# Adafruit_WICED_WiFi_Feather.net
KiCad netlist of a schematic drawn in EAGLE
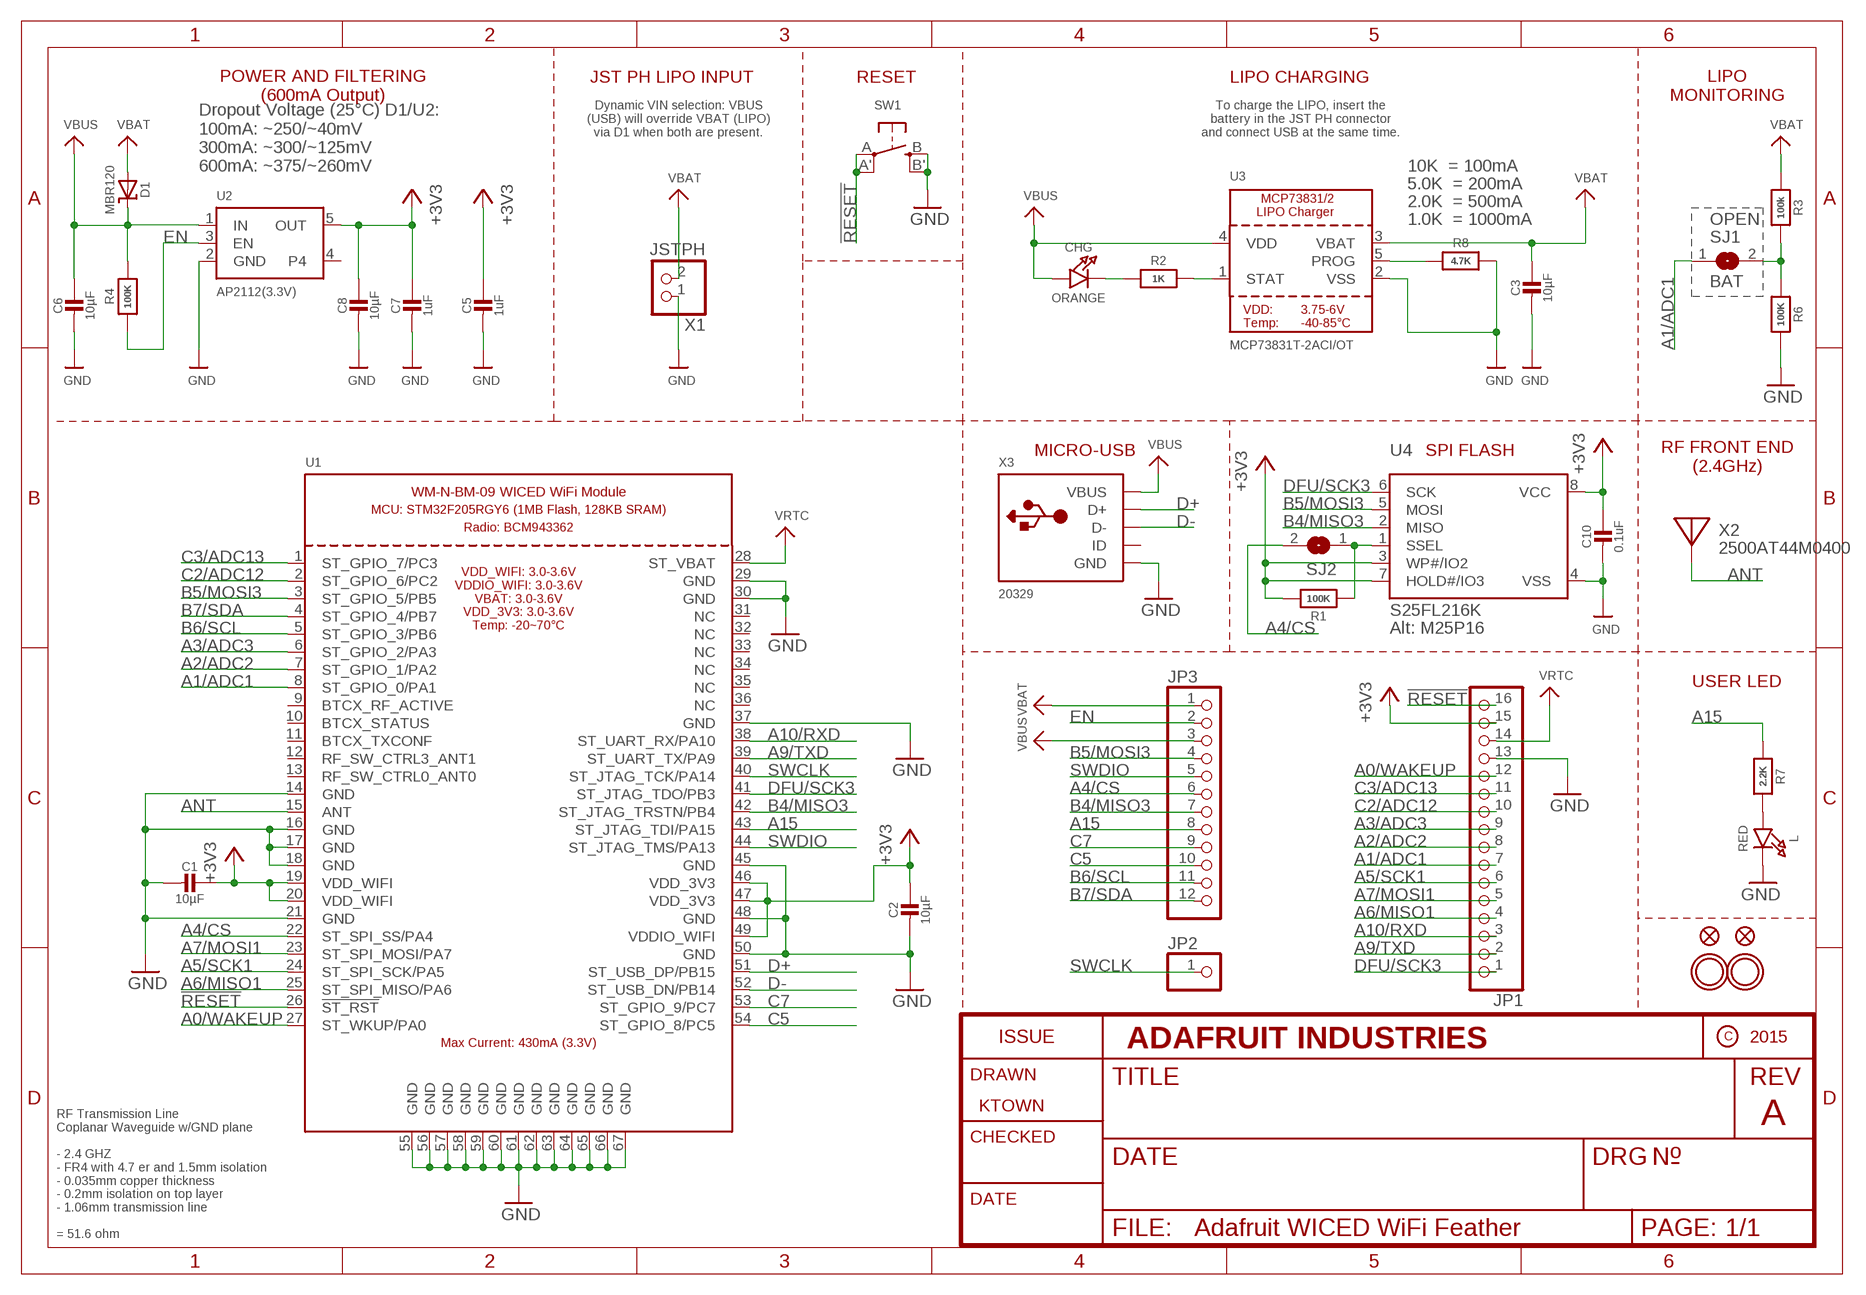
[diagram p0: schematic, sheet 1]

(export (version "E")
  (design (tool "Eeschema 10.0.6"))
  (components
    (comp (ref "C1")
      (value "10µF")
      (footprint "eagle-import:0805-NO")
      (libsource (lib "eagle-import") (part "CAP_CERAMIC0805-NOOUTLINE"))
    )
    (comp (ref "C2")
      (value "10µF")
      (footprint "eagle-import:0805-NO")
      (libsource (lib "eagle-import") (part "CAP_CERAMIC0805-NOOUTLINE"))
    )
    (comp (ref "C3")
      (value "10µF")
      (footprint "eagle-import:0805-NO")
      (libsource (lib "eagle-import") (part "CAP_CERAMIC0805-NOOUTLINE"))
    )
    (comp (ref "C5")
      (value "1uF")
      (footprint "eagle-import:0603-NO")
      (libsource (lib "eagle-import") (part "CAP_CERAMIC0603_NO"))
    )
    (comp (ref "C6")
      (value "10µF")
      (footprint "eagle-import:0805-NO")
      (libsource (lib "eagle-import") (part "CAP_CERAMIC0805-NOOUTLINE"))
    )
    (comp (ref "C7")
      (value "1uF")
      (footprint "eagle-import:0603-NO")
      (libsource (lib "eagle-import") (part "CAP_CERAMIC0603_NO"))
    )
    (comp (ref "C8")
      (value "10µF")
      (footprint "eagle-import:0805-NO")
      (libsource (lib "eagle-import") (part "CAP_CERAMIC0805-NOOUTLINE"))
    )
    (comp (ref "C10")
      (value "0.1uF")
      (footprint "eagle-import:0805_10MGAP")
      (libsource (lib "eagle-import") (part "CAP_CERAMIC0805_10MGAP"))
    )
    (comp (ref "CHG")
      (value "ORANGE")
      (footprint "eagle-import:CHIPLED_0805_NOOUTLINE")
      (libsource (lib "eagle-import") (part "LED0805_NOOUTLINE"))
    )
    (comp (ref "D1")
      (value "MBR120")
      (footprint "eagle-import:SOD-123")
      (libsource (lib "eagle-import") (part "DIODE-SCHOTTKYSOD-123"))
    )
    (comp (ref "JP1")
      (value "HEADER-1X16ROUND")
      (footprint "eagle-import:1X16_ROUND")
      (libsource (lib "eagle-import") (part "HEADER-1X16ROUND"))
    )
    (comp (ref "JP2")
      (value "HEADER-1X1ROUND")
      (footprint "eagle-import:1X01_ROUND")
      (libsource (lib "eagle-import") (part "HEADER-1X1ROUND"))
    )
    (comp (ref "JP3")
      (value "HEADER-1X12")
      (footprint "eagle-import:1X12_ROUND")
      (libsource (lib "eagle-import") (part "HEADER-1X12"))
    )
    (comp (ref "L")
      (value "RED")
      (footprint "eagle-import:CHIPLED_0805_NOOUTLINE")
      (libsource (lib "eagle-import") (part "LED0805_NOOUTLINE"))
    )
    (comp (ref "R1")
      (value "100K")
      (footprint "eagle-import:0603-NO")
      (libsource (lib "eagle-import") (part "RESISTOR_0603_NOOUT"))
    )
    (comp (ref "R2")
      (value "1K")
      (footprint "eagle-import:0603-NO")
      (libsource (lib "eagle-import") (part "RESISTOR_0603_NOOUT"))
    )
    (comp (ref "R3")
      (value "100k")
      (footprint "eagle-import:0603-NO")
      (libsource (lib "eagle-import") (part "RESISTOR_0603_NOOUT"))
    )
    (comp (ref "R4")
      (value "100K")
      (footprint "eagle-import:0603-NO")
      (libsource (lib "eagle-import") (part "RESISTOR_0603_NOOUT"))
    )
    (comp (ref "R6")
      (value "100K")
      (footprint "eagle-import:0603-NO")
      (libsource (lib "eagle-import") (part "RESISTOR_0603_NOOUT"))
    )
    (comp (ref "R7")
      (value "2.2K")
      (footprint "eagle-import:0603-NO")
      (libsource (lib "eagle-import") (part "RESISTOR_0603_NOOUT"))
    )
    (comp (ref "R8")
      (value "4.7K")
      (footprint "eagle-import:0603-NO")
      (libsource (lib "eagle-import") (part "RESISTOR_0603_NOOUT"))
    )
    (comp (ref "SJ1")
      (value "BAT")
      (footprint "eagle-import:SOLDERJUMPER_REFLOW_NOPASTE")
      (libsource (lib "eagle-import") (part "SOLDERJUMPERREFLOW_NOPASTE"))
    )
    (comp (ref "SJ2")
      (value "SOLDERJUMPER")
      (footprint "eagle-import:SOLDERJUMPER_ARROW_NOPASTE")
      (libsource (lib "eagle-import") (part "SOLDERJUMPER"))
    )
    (comp (ref "SW1")
      (value "SWITCH_TACT_SMT4.6X2.8")
      (footprint "eagle-import:BTN_KMR2_4.6X2.8")
      (libsource (lib "eagle-import") (part "SWITCH_TACT_SMT4.6X2.8"))
    )
    (comp (ref "U$31")
      (value "MOUNTINGHOLE2.5")
      (footprint "eagle-import:MOUNTINGHOLE_2.5_PLATED")
      (libsource (lib "eagle-import") (part "MOUNTINGHOLE2.5"))
    )
    (comp (ref "U$32")
      (value "MOUNTINGHOLE2.5")
      (footprint "eagle-import:MOUNTINGHOLE_2.5_PLATED")
      (libsource (lib "eagle-import") (part "MOUNTINGHOLE2.5"))
    )
    (comp (ref "U$34")
      (value "FIDUCIAL\"\"")
      (footprint "eagle-import:FIDUCIAL_1MM")
      (libsource (lib "eagle-import") (part "FIDUCIAL{dblquote}{dblquote}"))
    )
    (comp (ref "U$35")
      (value "FIDUCIAL\"\"")
      (footprint "eagle-import:FIDUCIAL_1MM")
      (libsource (lib "eagle-import") (part "FIDUCIAL{dblquote}{dblquote}"))
    )
    (comp (ref "U1")
      (value "USI_WM-N-BM-09")
      (footprint "eagle-import:USI_WM-N-BM-09")
      (libsource (lib "eagle-import") (part "USI_WM-N-BM-09"))
    )
    (comp (ref "U2")
      (value "AP2112(3.3V)")
      (footprint "eagle-import:SOT23-5")
      (libsource (lib "eagle-import") (part "VREG_SOT23-5"))
    )
    (comp (ref "U3")
      (value "MCP73831T-2ACI/OT")
      (footprint "eagle-import:SOT23-5")
      (libsource (lib "eagle-import") (part "MCP73831/2"))
    )
    (comp (ref "U4")
      (value "S25FL216K")
      (footprint "eagle-import:SOIC8_150MIL")
      (libsource (lib "eagle-import") (part "SPIFLASH_SOIC8"))
    )
    (comp (ref "X1")
      (value "JSTPH")
      (footprint "eagle-import:JSTPH2")
      (libsource (lib "eagle-import") (part "CON_JST_PH_2PIN"))
    )
    (comp (ref "X2")
      (value "2500AT44M0400")
      (footprint "eagle-import:ANT_2500AT44M0400")
      (libsource (lib "eagle-import") (part "ANTENNA_JOHANSON_2500AT44M0400"))
    )
    (comp (ref "X3")
      (value "20329")
      (footprint "eagle-import:4UCONN_20329_V2")
      (libsource (lib "eagle-import") (part "USB_MICRO_20329_V2"))
    )
  )
  (nets
    (net (code "1") (name "+3V3") (class "Default")
      (node (ref "C1") (pin "1") (pinfunction "1_1") (pintype "passive"))
      (node (ref "C10") (pin "1") (pinfunction "1_1") (pintype "passive"))
      (node (ref "C2") (pin "1") (pinfunction "1_1") (pintype "passive"))
      (node (ref "C5") (pin "1") (pinfunction "1_1") (pintype "passive"))
      (node (ref "C7") (pin "1") (pinfunction "1_1") (pintype "passive"))
      (node (ref "C8") (pin "1") (pinfunction "1_1") (pintype "passive"))
      (node (ref "JP1") (pin "15") (pinfunction "15_15") (pintype "passive"))
      (node (ref "R1") (pin "2") (pinfunction "2_2") (pintype "passive"))
      (node (ref "U1") (pin "19") (pinfunction "VDD_WIFI_19") (pintype "power_in"))
      (node (ref "U1") (pin "20") (pinfunction "VDD_WIFI_20") (pintype "power_in"))
      (node (ref "U1") (pin "46") (pinfunction "VDD_3V3_46") (pintype "power_in"))
      (node (ref "U1") (pin "47") (pinfunction "VDD_3V3_47") (pintype "power_in"))
      (node (ref "U1") (pin "49") (pinfunction "VDDIO_WIFI_49") (pintype "power_in"))
      (node (ref "U2") (pin "5") (pinfunction "OUT_5") (pintype "power_in"))
      (node (ref "U4") (pin "3") (pinfunction "WP#/IO2_3") (pintype "bidirectional"))
      (node (ref "U4") (pin "7") (pinfunction "HOLD#/IO3_7") (pintype "bidirectional"))
      (node (ref "U4") (pin "8") (pinfunction "VCC_8") (pintype "bidirectional"))
    )
    (net (code "2") (name "/A0{slash}WAKEUP") (class "Default")
      (node (ref "JP1") (pin "12") (pinfunction "12_12") (pintype "passive"))
      (node (ref "U1") (pin "27") (pinfunction "ST_WKUP/PA0_27") (pintype "bidirectional"))
    )
    (net (code "3") (name "/A1{slash}ADC1") (class "Default")
      (node (ref "JP1") (pin "7") (pinfunction "7_7") (pintype "passive"))
      (node (ref "SJ1") (pin "1") (pinfunction "1_1") (pintype "passive"))
      (node (ref "U1") (pin "8") (pinfunction "ST_GPIO_0/PA1_8") (pintype "bidirectional"))
    )
    (net (code "4") (name "/A2{slash}ADC2") (class "Default")
      (node (ref "JP1") (pin "8") (pinfunction "8_8") (pintype "passive"))
      (node (ref "U1") (pin "7") (pinfunction "ST_GPIO_1/PA2_7") (pintype "bidirectional"))
    )
    (net (code "5") (name "/A3{slash}ADC3") (class "Default")
      (node (ref "JP1") (pin "9") (pinfunction "9_9") (pintype "passive"))
      (node (ref "U1") (pin "6") (pinfunction "ST_GPIO_2/PA3_6") (pintype "bidirectional"))
    )
    (net (code "6") (name "/A4{slash}CS") (class "Default")
      (node (ref "JP3") (pin "6") (pinfunction "6_6") (pintype "passive"))
      (node (ref "SJ2") (pin "2") (pinfunction "2_2") (pintype "passive"))
      (node (ref "U1") (pin "22") (pinfunction "ST_SPI_SS/PA4_22") (pintype "bidirectional"))
    )
    (net (code "7") (name "/A5{slash}SCK1") (class "Default")
      (node (ref "JP1") (pin "6") (pinfunction "6_6") (pintype "passive"))
      (node (ref "U1") (pin "24") (pinfunction "ST_SPI_SCK/PA5_24") (pintype "bidirectional"))
    )
    (net (code "8") (name "/A6{slash}MISO1") (class "Default")
      (node (ref "JP1") (pin "4") (pinfunction "4_4") (pintype "passive"))
      (node (ref "U1") (pin "25") (pinfunction "ST_SPI_MISO/PA6_25") (pintype "bidirectional"))
    )
    (net (code "9") (name "/A7{slash}MOSI1") (class "Default")
      (node (ref "JP1") (pin "5") (pinfunction "5_5") (pintype "passive"))
      (node (ref "U1") (pin "23") (pinfunction "ST_SPI_MOSI/PA7_23") (pintype "bidirectional"))
    )
    (net (code "10") (name "/A9{slash}TXD") (class "Default")
      (node (ref "JP1") (pin "2") (pinfunction "2_2") (pintype "passive"))
      (node (ref "U1") (pin "39") (pinfunction "ST_UART_TX/PA9_39") (pintype "bidirectional"))
    )
    (net (code "11") (name "/A10{slash}RXD") (class "Default")
      (node (ref "JP1") (pin "3") (pinfunction "3_3") (pintype "passive"))
      (node (ref "U1") (pin "38") (pinfunction "ST_UART_RX/PA10_38") (pintype "bidirectional"))
    )
    (net (code "12") (name "/A15") (class "Default")
      (node (ref "JP3") (pin "8") (pinfunction "8_8") (pintype "passive"))
      (node (ref "R7") (pin "1") (pinfunction "1_1") (pintype "passive"))
      (node (ref "U1") (pin "43") (pinfunction "ST_JTAG_TDI/PA15_43") (pintype "bidirectional"))
    )
    (net (code "13") (name "/ANT") (class "Default")
      (node (ref "U1") (pin "15") (pinfunction "ANT_15") (pintype "bidirectional"))
      (node (ref "X2") (pin "FEED") (pinfunction "P$1_FEED") (pintype "passive"))
    )
    (net (code "14") (name "/B4{slash}MISO3") (class "Default")
      (node (ref "JP3") (pin "7") (pinfunction "7_7") (pintype "passive"))
      (node (ref "U1") (pin "42") (pinfunction "ST_JTAG_TRSTN/PB4_42") (pintype "bidirectional"))
      (node (ref "U4") (pin "2") (pinfunction "MISO_2") (pintype "bidirectional"))
    )
    (net (code "15") (name "/B5{slash}MOSI3") (class "Default")
      (node (ref "JP3") (pin "4") (pinfunction "4_4") (pintype "passive"))
      (node (ref "U1") (pin "3") (pinfunction "ST_GPIO_5/PB5_3") (pintype "bidirectional"))
      (node (ref "U4") (pin "5") (pinfunction "MOSI_5") (pintype "bidirectional"))
    )
    (net (code "16") (name "/B6{slash}SCL") (class "Default")
      (node (ref "JP3") (pin "11") (pinfunction "11_11") (pintype "passive"))
      (node (ref "U1") (pin "5") (pinfunction "ST_GPIO_3/PB6_5") (pintype "bidirectional"))
    )
    (net (code "17") (name "/B7{slash}SDA") (class "Default")
      (node (ref "JP3") (pin "12") (pinfunction "12_12") (pintype "passive"))
      (node (ref "U1") (pin "4") (pinfunction "ST_GPIO_4/PB7_4") (pintype "bidirectional"))
    )
    (net (code "18") (name "/C2{slash}ADC12") (class "Default")
      (node (ref "JP1") (pin "10") (pinfunction "10_10") (pintype "passive"))
      (node (ref "U1") (pin "2") (pinfunction "ST_GPIO_6/PC2_2") (pintype "bidirectional"))
    )
    (net (code "19") (name "/C3{slash}ADC13") (class "Default")
      (node (ref "JP1") (pin "11") (pinfunction "11_11") (pintype "passive"))
      (node (ref "U1") (pin "1") (pinfunction "ST_GPIO_7/PC3_1") (pintype "bidirectional"))
    )
    (net (code "20") (name "/C5") (class "Default")
      (node (ref "JP3") (pin "10") (pinfunction "10_10") (pintype "passive"))
      (node (ref "U1") (pin "54") (pinfunction "ST_GPIO_8/PC5_54") (pintype "bidirectional"))
    )
    (net (code "21") (name "/C7") (class "Default")
      (node (ref "JP3") (pin "9") (pinfunction "9_9") (pintype "passive"))
      (node (ref "U1") (pin "53") (pinfunction "ST_GPIO_9/PC7_53") (pintype "bidirectional"))
    )
    (net (code "22") (name "/D+") (class "Default")
      (node (ref "U1") (pin "51") (pinfunction "ST_USB_DP/PB15_51") (pintype "bidirectional"))
      (node (ref "X3") (pin "D+") (pinfunction "D+_D+") (pintype "bidirectional"))
    )
    (net (code "23") (name "/D-") (class "Default")
      (node (ref "U1") (pin "52") (pinfunction "ST_USB_DN/PB14_52") (pintype "bidirectional"))
      (node (ref "X3") (pin "D-") (pinfunction "D-_D-") (pintype "bidirectional"))
    )
    (net (code "24") (name "/DFU{slash}SCK3") (class "Default")
      (node (ref "JP1") (pin "1") (pinfunction "1_1") (pintype "passive"))
      (node (ref "U1") (pin "41") (pinfunction "ST_JTAG_TDO/PB3_41") (pintype "bidirectional"))
      (node (ref "U4") (pin "6") (pinfunction "SCK_6") (pintype "bidirectional"))
    )
    (net (code "25") (name "/EN") (class "Default")
      (node (ref "JP3") (pin "2") (pinfunction "2_2") (pintype "passive"))
      (node (ref "R4") (pin "1") (pinfunction "1_1") (pintype "passive"))
      (node (ref "U2") (pin "3") (pinfunction "EN_3") (pintype "input"))
    )
    (net (code "26") (name "/SWCLK") (class "Default")
      (node (ref "JP2") (pin "1") (pinfunction "1_1") (pintype "passive"))
      (node (ref "U1") (pin "40") (pinfunction "ST_JTAG_TCK/PA14_40") (pintype "bidirectional"))
    )
    (net (code "27") (name "/SWDIO") (class "Default")
      (node (ref "JP3") (pin "5") (pinfunction "5_5") (pintype "passive"))
      (node (ref "U1") (pin "44") (pinfunction "ST_JTAG_TMS/PA13_44") (pintype "bidirectional"))
    )
    (net (code "28") (name "/~{RESET}") (class "Default")
      (node (ref "JP1") (pin "16") (pinfunction "16_16") (pintype "passive"))
      (node (ref "SW1") (pin "A") (pinfunction "P_A") (pintype "passive"))
      (node (ref "SW1") (pin "A'") (pinfunction "P1_A'") (pintype "passive"))
      (node (ref "U1") (pin "26") (pinfunction "~{ST_RST}_26") (pintype "bidirectional"))
    )
    (net (code "29") (name "GND") (class "Default")
      (node (ref "C1") (pin "2") (pinfunction "2_2") (pintype "passive"))
      (node (ref "C10") (pin "2") (pinfunction "2_2") (pintype "passive"))
      (node (ref "C2") (pin "2") (pinfunction "2_2") (pintype "passive"))
      (node (ref "C3") (pin "2") (pinfunction "2_2") (pintype "passive"))
      (node (ref "C5") (pin "2") (pinfunction "2_2") (pintype "passive"))
      (node (ref "C6") (pin "2") (pinfunction "2_2") (pintype "passive"))
      (node (ref "C7") (pin "2") (pinfunction "2_2") (pintype "passive"))
      (node (ref "C8") (pin "2") (pinfunction "2_2") (pintype "passive"))
      (node (ref "JP1") (pin "13") (pinfunction "13_13") (pintype "passive"))
      (node (ref "L") (pin "C") (pinfunction "C_C") (pintype "passive"))
      (node (ref "R6") (pin "2") (pinfunction "2_2") (pintype "passive"))
      (node (ref "R8") (pin "2") (pinfunction "2_2") (pintype "passive"))
      (node (ref "SW1") (pin "B") (pinfunction "S_B") (pintype "passive"))
      (node (ref "SW1") (pin "B'") (pinfunction "S1_B'") (pintype "passive"))
      (node (ref "U1") (pin "14") (pinfunction "GND_14") (pintype "power_in"))
      (node (ref "U1") (pin "16") (pinfunction "GND_16") (pintype "power_in"))
      (node (ref "U1") (pin "17") (pinfunction "GND_17") (pintype "power_in"))
      (node (ref "U1") (pin "18") (pinfunction "GND_18") (pintype "power_in"))
      (node (ref "U1") (pin "21") (pinfunction "GND_21") (pintype "power_in"))
      (node (ref "U1") (pin "29") (pinfunction "GND_29") (pintype "power_in"))
      (node (ref "U1") (pin "30") (pinfunction "GND_30") (pintype "power_in"))
      (node (ref "U1") (pin "37") (pinfunction "GND_37") (pintype "power_in"))
      (node (ref "U1") (pin "45") (pinfunction "GND_45") (pintype "power_in"))
      (node (ref "U1") (pin "48") (pinfunction "GND_48") (pintype "power_in"))
      (node (ref "U1") (pin "50") (pinfunction "GND_50") (pintype "power_in"))
      (node (ref "U1") (pin "55") (pinfunction "GND_55") (pintype "power_in"))
      (node (ref "U1") (pin "56") (pinfunction "GND_56") (pintype "power_in"))
      (node (ref "U1") (pin "57") (pinfunction "GND_57") (pintype "power_in"))
      (node (ref "U1") (pin "58") (pinfunction "GND_58") (pintype "power_in"))
      (node (ref "U1") (pin "59") (pinfunction "GND_59") (pintype "power_in"))
      (node (ref "U1") (pin "60") (pinfunction "GND_60") (pintype "power_in"))
      (node (ref "U1") (pin "61") (pinfunction "GND_61") (pintype "power_in"))
      (node (ref "U1") (pin "62") (pinfunction "GND_62") (pintype "power_in"))
      (node (ref "U1") (pin "63") (pinfunction "GND_63") (pintype "power_in"))
      (node (ref "U1") (pin "64") (pinfunction "GND_64") (pintype "power_in"))
      (node (ref "U1") (pin "65") (pinfunction "GND_65") (pintype "power_in"))
      (node (ref "U1") (pin "66") (pinfunction "GND_66") (pintype "power_in"))
      (node (ref "U1") (pin "67") (pinfunction "GND_67") (pintype "power_in"))
      (node (ref "U2") (pin "2") (pinfunction "GND_2") (pintype "power_in"))
      (node (ref "U3") (pin "2") (pinfunction "VSS_2") (pintype "power_in"))
      (node (ref "U4") (pin "4") (pinfunction "VSS_4") (pintype "bidirectional"))
      (node (ref "X1") (pin "1") (pinfunction "1_1") (pintype "passive"))
      (node (ref "X3") (pin "BASE@1") (pinfunction "GND_BASE@1") (pintype "power_in"))
      (node (ref "X3") (pin "BASE@2") (pinfunction "GND_BASE@2") (pintype "power_in"))
      (node (ref "X3") (pin "GND") (pinfunction "GND_GND") (pintype "power_in"))
      (node (ref "X3") (pin "SPRT@1") (pinfunction "GND_SPRT@1") (pintype "power_in"))
      (node (ref "X3") (pin "SPRT@2") (pinfunction "GND_SPRT@2") (pintype "power_in"))
      (node (ref "X3") (pin "SPRT@3") (pinfunction "GND_SPRT@3") (pintype "power_in"))
      (node (ref "X3") (pin "SPRT@4") (pinfunction "GND_SPRT@4") (pintype "power_in"))
    )
    (net (code "30") (name "Net-(CHG-PadC)") (class "Default")
      (node (ref "CHG") (pin "C") (pinfunction "C_C") (pintype "passive"))
      (node (ref "R2") (pin "1") (pinfunction "1_1") (pintype "passive"))
    )
    (net (code "31") (name "Net-(L-PadA)") (class "Default")
      (node (ref "L") (pin "A") (pinfunction "A_A") (pintype "passive"))
      (node (ref "R7") (pin "2") (pinfunction "2_2") (pintype "passive"))
    )
    (net (code "32") (name "Net-(R3-Pad2)") (class "Default")
      (node (ref "R3") (pin "2") (pinfunction "2_2") (pintype "passive"))
      (node (ref "R6") (pin "1") (pinfunction "1_1") (pintype "passive"))
      (node (ref "SJ1") (pin "2") (pinfunction "2_2") (pintype "passive"))
    )
    (net (code "33") (name "Net-(U3-PROG)") (class "Default")
      (node (ref "R8") (pin "1") (pinfunction "1_1") (pintype "passive"))
      (node (ref "U3") (pin "5") (pinfunction "PROG_5") (pintype "input"))
    )
    (net (code "34") (name "Net-(U3-STAT)") (class "Default")
      (node (ref "R2") (pin "2") (pinfunction "2_2") (pintype "passive"))
      (node (ref "U3") (pin "1") (pinfunction "STAT_1") (pintype "output"))
    )
    (net (code "35") (name "Net-(U4-SSEL)") (class "Default")
      (node (ref "R1") (pin "1") (pinfunction "1_1") (pintype "passive"))
      (node (ref "SJ2") (pin "1") (pinfunction "1_1") (pintype "passive"))
      (node (ref "U4") (pin "1") (pinfunction "SSEL_1") (pintype "bidirectional"))
    )
    (net (code "36") (name "VBAT") (class "Default")
      (node (ref "C3") (pin "1") (pinfunction "1_1") (pintype "passive"))
      (node (ref "D1") (pin "A") (pinfunction "A_A") (pintype "passive"))
      (node (ref "JP3") (pin "1") (pinfunction "1_1") (pintype "passive"))
      (node (ref "R3") (pin "1") (pinfunction "1_1") (pintype "passive"))
      (node (ref "U3") (pin "3") (pinfunction "VBAT_3") (pintype "power_in"))
      (node (ref "X1") (pin "2") (pinfunction "2_2") (pintype "passive"))
    )
    (net (code "37") (name "VBUS") (class "Default")
      (node (ref "C6") (pin "1") (pinfunction "1_1") (pintype "passive"))
      (node (ref "CHG") (pin "A") (pinfunction "A_A") (pintype "passive"))
      (node (ref "D1") (pin "C") (pinfunction "C_C") (pintype "passive"))
      (node (ref "JP3") (pin "3") (pinfunction "3_3") (pintype "passive"))
      (node (ref "R4") (pin "2") (pinfunction "2_2") (pintype "passive"))
      (node (ref "U2") (pin "1") (pinfunction "IN_1") (pintype "power_in"))
      (node (ref "U3") (pin "4") (pinfunction "VDD_4") (pintype "power_in"))
      (node (ref "X3") (pin "VBUS") (pinfunction "VBUS_VBUS") (pintype "power_in"))
    )
    (net (code "38") (name "VRTC") (class "Default")
      (node (ref "JP1") (pin "14") (pinfunction "14_14") (pintype "passive"))
      (node (ref "U1") (pin "28") (pinfunction "ST_VBAT_28") (pintype "power_in"))
    )
    (net (code "39") (name "unconnected-(U1-BTCX_RF_ACTIVE-Pad9)") (class "Default")
      (node (ref "U1") (pin "9") (pinfunction "BTCX_RF_ACTIVE_9") (pintype "input"))
    )
    (net (code "40") (name "unconnected-(U1-BTCX_STATUS-Pad10)") (class "Default")
      (node (ref "U1") (pin "10") (pinfunction "BTCX_STATUS_10") (pintype "input"))
    )
    (net (code "41") (name "unconnected-(U1-BTCX_TXCONF-Pad11)") (class "Default")
      (node (ref "U1") (pin "11") (pinfunction "BTCX_TXCONF_11") (pintype "output"))
    )
    (net (code "42") (name "unconnected-(U1-NC-Pad31)") (class "Default")
      (node (ref "U1") (pin "31") (pinfunction "NC_31") (pintype "no_connect"))
    )
    (net (code "43") (name "unconnected-(U1-NC-Pad32)") (class "Default")
      (node (ref "U1") (pin "32") (pinfunction "NC_32") (pintype "no_connect"))
    )
    (net (code "44") (name "unconnected-(U1-NC-Pad33)") (class "Default")
      (node (ref "U1") (pin "33") (pinfunction "NC_33") (pintype "no_connect"))
    )
    (net (code "45") (name "unconnected-(U1-NC-Pad34)") (class "Default")
      (node (ref "U1") (pin "34") (pinfunction "NC_34") (pintype "no_connect"))
    )
    (net (code "46") (name "unconnected-(U1-NC-Pad35)") (class "Default")
      (node (ref "U1") (pin "35") (pinfunction "NC_35") (pintype "no_connect"))
    )
    (net (code "47") (name "unconnected-(U1-NC-Pad36)") (class "Default")
      (node (ref "U1") (pin "36") (pinfunction "NC_36") (pintype "no_connect"))
    )
    (net (code "48") (name "unconnected-(U1-RF_SW_CTRL0_ANT0-Pad13)") (class "Default")
      (node (ref "U1") (pin "13") (pinfunction "RF_SW_CTRL0_ANT0_13") (pintype "output"))
    )
    (net (code "49") (name "unconnected-(U1-RF_SW_CTRL3_ANT1-Pad12)") (class "Default")
      (node (ref "U1") (pin "12") (pinfunction "RF_SW_CTRL3_ANT1_12") (pintype "output"))
    )
    (net (code "50") (name "unconnected-(U2-P4-Pad4)") (class "Default")
      (node (ref "U2") (pin "4") (pinfunction "P4_4") (pintype "bidirectional"))
    )
    (net (code "51") (name "unconnected-(X3-PadID)") (class "Default")
      (node (ref "X3") (pin "ID") (pinfunction "ID_ID") (pintype "bidirectional"))
    )
  )
)
